# WallDigitalClock.net
KiCad netlist of a schematic drawn in Altium Designer
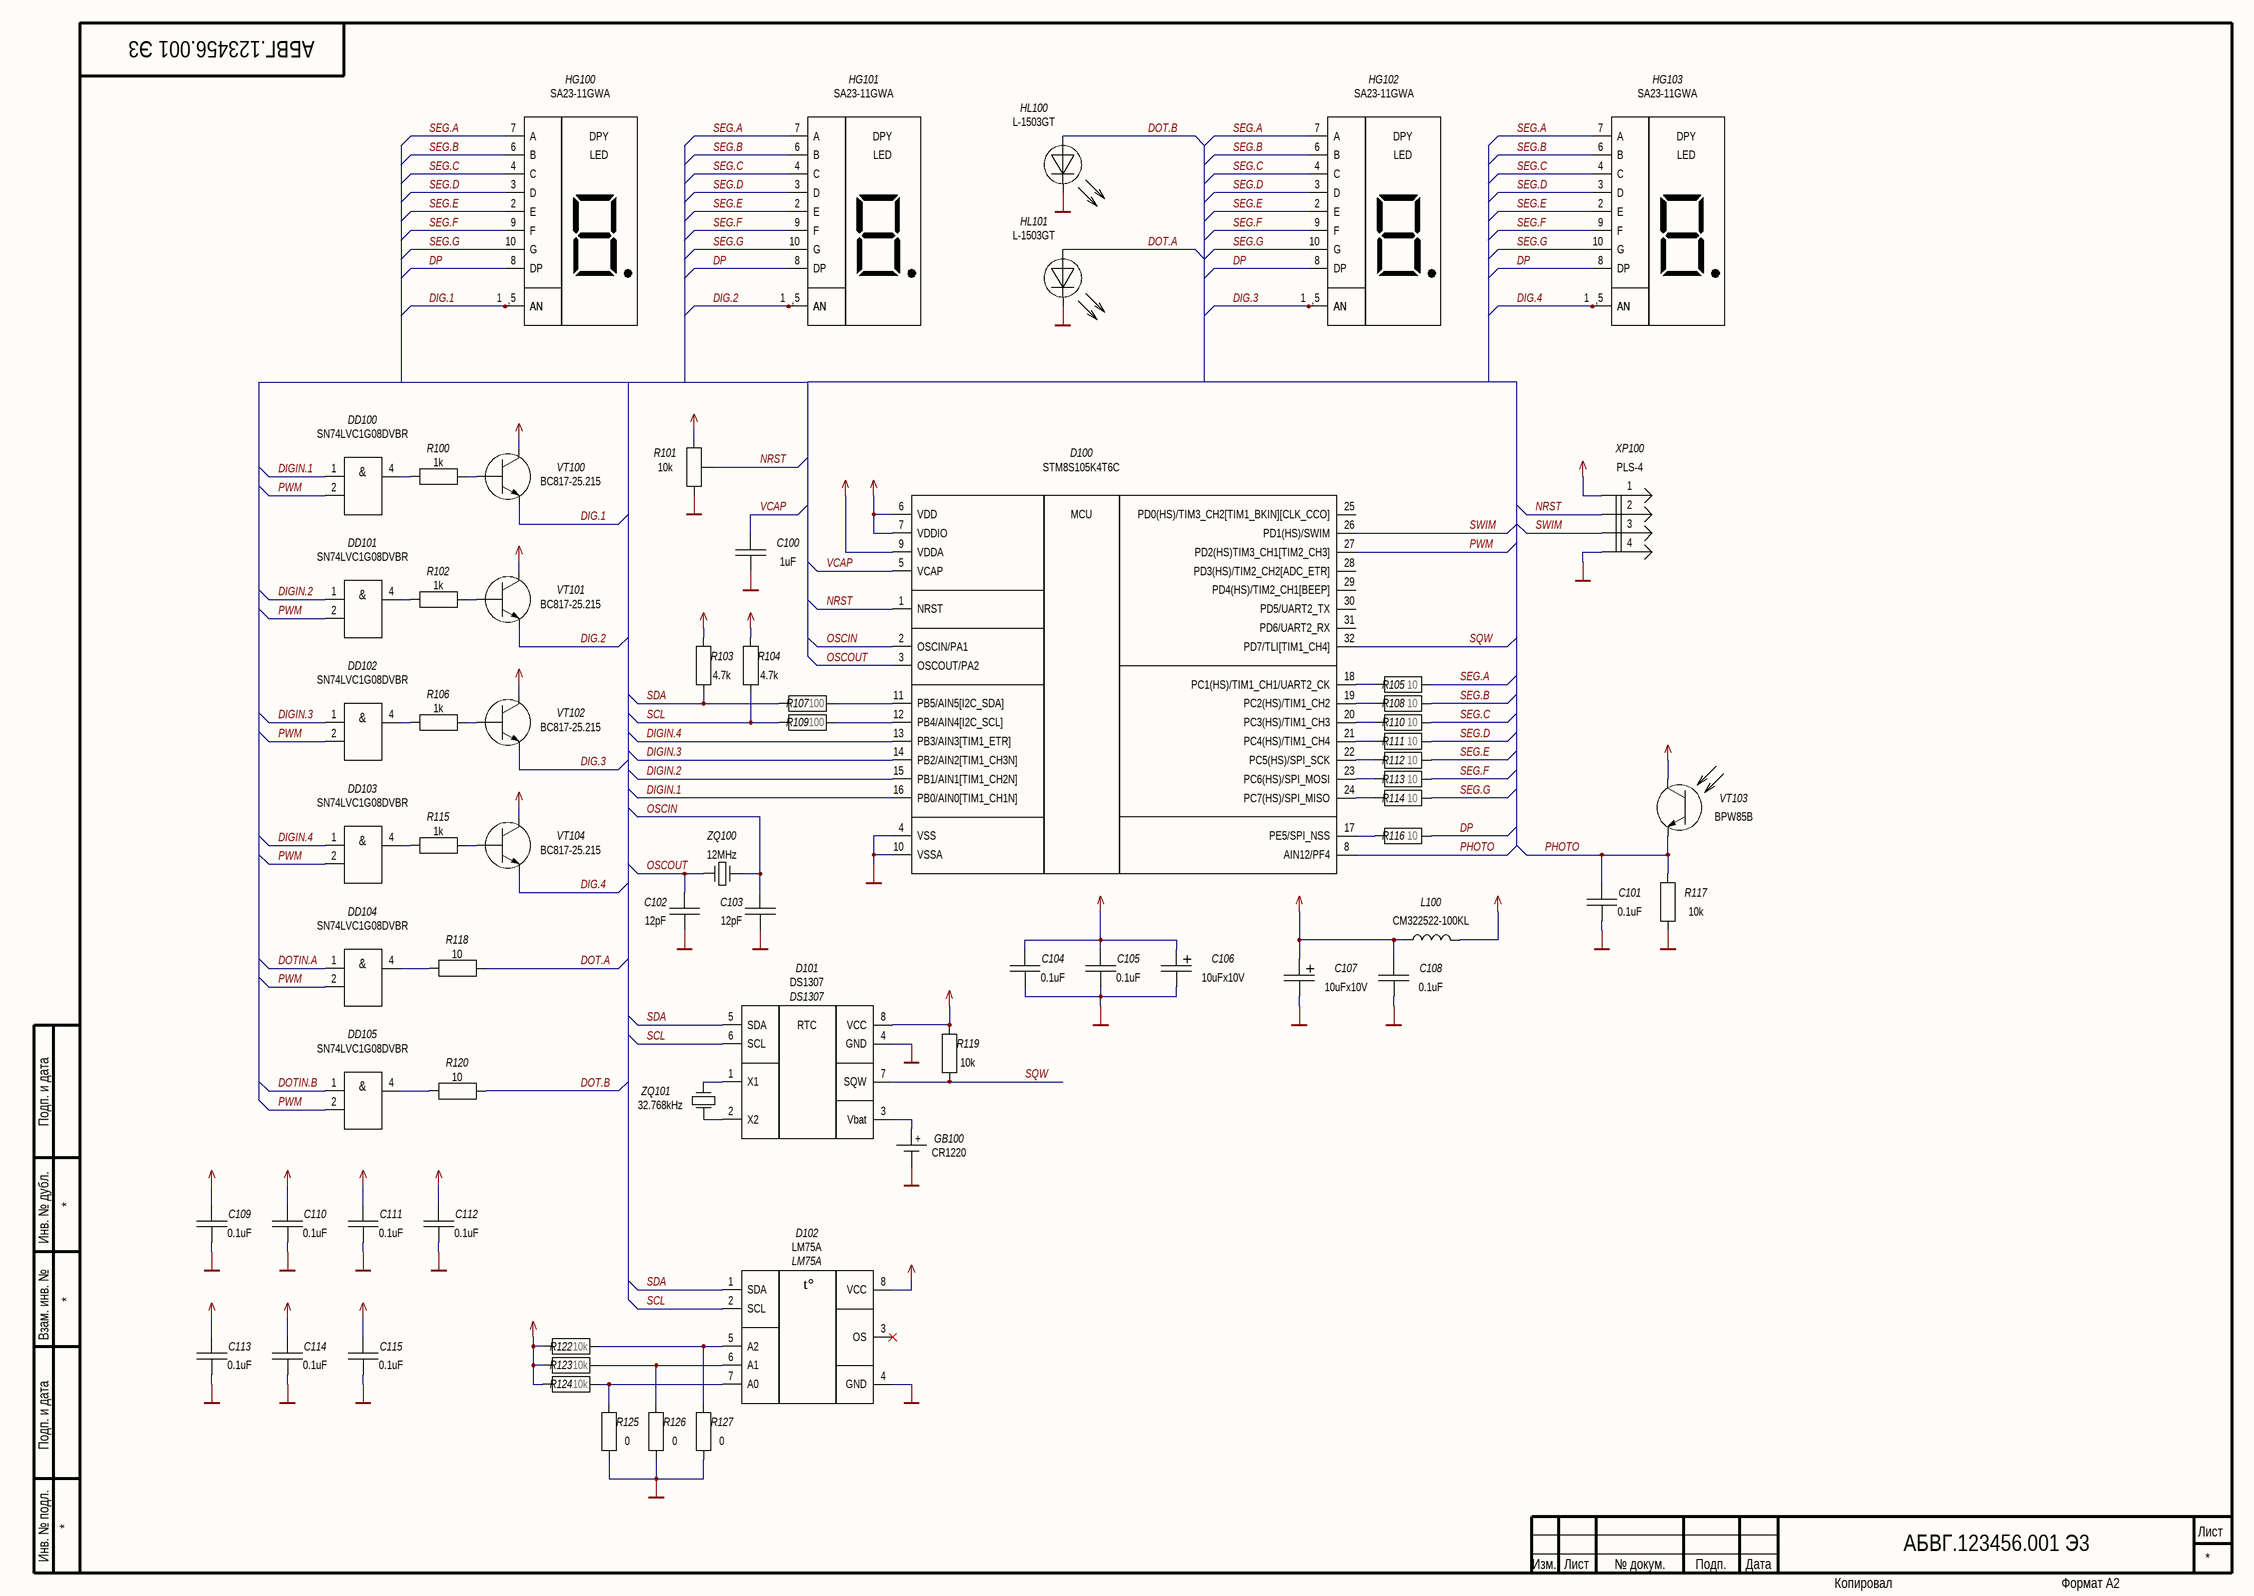
[diagram p0: WallDigitalClock.SchDoc]

(export (version "E")
  (design (tool "Eeschema 10.0.6"))
  (components
    (comp (ref "C100")
      (value "1uF")
      (footprint "CAP0603RS")
      (fields (field (name "Comment") "Capacitor"))
      (libsource (lib "Capacitor") (part "Capacitor"))
    )
    (comp (ref "C101")
      (value "0.1uF")
      (footprint "CAP0603RS")
      (fields (field (name "Comment") "Capacitor"))
      (libsource (lib "Capacitor") (part "Capacitor"))
    )
    (comp (ref "C102")
      (value "12pF")
      (footprint "CAP0603RS")
      (fields (field (name "Comment") "Capacitor"))
      (libsource (lib "Capacitor") (part "Capacitor"))
    )
    (comp (ref "C103")
      (value "12pF")
      (footprint "CAP0603RS")
      (fields (field (name "Comment") "Capacitor"))
      (libsource (lib "Capacitor") (part "Capacitor"))
    )
    (comp (ref "C104")
      (value "0.1uF")
      (footprint "CAP0603RS")
      (fields (field (name "Comment") "Capacitor"))
      (libsource (lib "Capacitor") (part "Capacitor"))
    )
    (comp (ref "C105")
      (value "0.1uF")
      (footprint "CAP0603RS")
      (fields (field (name "Comment") "Capacitor"))
      (libsource (lib "Capacitor") (part "Capacitor"))
    )
    (comp (ref "C106")
      (value "10uFx10V")
      (footprint "Type-C")
      (fields (field (name "MANUFACTURER") "Vishay") (field (name "Comment") "Capacitor_Pol"))
      (libsource (lib "Capacitor") (part "Capacitor_Pol"))
    )
    (comp (ref "C107")
      (value "10uFx10V")
      (footprint "Type-C")
      (fields (field (name "MANUFACTURER") "Vishay") (field (name "Comment") "Capacitor_Pol"))
      (libsource (lib "Capacitor") (part "Capacitor_Pol"))
    )
    (comp (ref "C108")
      (value "0.1uF")
      (footprint "CAP0603RS")
      (fields (field (name "Comment") "Capacitor"))
      (libsource (lib "Capacitor") (part "Capacitor"))
    )
    (comp (ref "C109")
      (value "0.1uF")
      (footprint "CAP0603RS")
      (fields (field (name "Comment") "Capacitor"))
      (libsource (lib "Capacitor") (part "Capacitor"))
    )
    (comp (ref "C110")
      (value "0.1uF")
      (footprint "CAP0603RS")
      (fields (field (name "Comment") "Capacitor"))
      (libsource (lib "Capacitor") (part "Capacitor"))
    )
    (comp (ref "C111")
      (value "0.1uF")
      (footprint "CAP0603RS")
      (fields (field (name "Comment") "Capacitor"))
      (libsource (lib "Capacitor") (part "Capacitor"))
    )
    (comp (ref "C112")
      (value "0.1uF")
      (footprint "CAP0603RS")
      (fields (field (name "Comment") "Capacitor"))
      (libsource (lib "Capacitor") (part "Capacitor"))
    )
    (comp (ref "C113")
      (value "0.1uF")
      (footprint "CAP0603RS")
      (fields (field (name "Comment") "Capacitor"))
      (libsource (lib "Capacitor") (part "Capacitor"))
    )
    (comp (ref "C114")
      (value "0.1uF")
      (footprint "CAP0603RS")
      (fields (field (name "Comment") "Capacitor"))
      (libsource (lib "Capacitor") (part "Capacitor"))
    )
    (comp (ref "C115")
      (value "0.1uF")
      (footprint "CAP0603RS")
      (fields (field (name "Comment") "Capacitor"))
      (libsource (lib "Capacitor") (part "Capacitor"))
    )
    (comp (ref "D100")
      (value "STM8S105K4T6C")
      (footprint "LQFP32")
      (description "MCU 8bit, STM8 CISC, Package LQFP-32")
      (fields (field (name "MANUFACTURER") "ST Microelectronics"))
      (libsource (lib "IC_STM8") (part "STM8S105K4T6C"))
    )
    (comp (ref "D101")
      (value "DS1307")
      (footprint "SO8")
      (description "Real-time clock (RTC)")
      (fields (field (name "ALTIUM_VALUE") "DS1307"))
      (libsource (lib "IC_Sensor") (part "DS1307"))
    )
    (comp (ref "D102")
      (value "LM75A")
      (footprint "SO8")
      (description "Digital temperature sensor and thermal watchdog")
      (fields (field (name "ALTIUM_VALUE") "LM75A"))
      (libsource (lib "IC_Sensor") (part "LM75A"))
    )
    (comp (ref "DD100")
      (value "SN74LVC1G08DVBR")
      (footprint "SOT23-5")
      (description "Single 2-Input Positive-AND Gate")
      (fields (field (name "MANUFACTURER") "Texas Instruments") (field (name "Comment") "SN74LVC1G08"))
      (libsource (lib "IC_Logic") (part "SN74LVC1G08"))
    )
    (comp (ref "DD101")
      (value "SN74LVC1G08DVBR")
      (footprint "SOT23-5")
      (description "Single 2-Input Positive-AND Gate")
      (fields (field (name "MANUFACTURER") "Texas Instruments") (field (name "Comment") "SN74LVC1G08"))
      (libsource (lib "IC_Logic") (part "SN74LVC1G08"))
    )
    (comp (ref "DD102")
      (value "SN74LVC1G08DVBR")
      (footprint "SOT23-5")
      (description "Single 2-Input Positive-AND Gate")
      (fields (field (name "MANUFACTURER") "Texas Instruments") (field (name "Comment") "SN74LVC1G08"))
      (libsource (lib "IC_Logic") (part "SN74LVC1G08"))
    )
    (comp (ref "DD103")
      (value "SN74LVC1G08DVBR")
      (footprint "SOT23-5")
      (description "Single 2-Input Positive-AND Gate")
      (fields (field (name "MANUFACTURER") "Texas Instruments") (field (name "Comment") "SN74LVC1G08"))
      (libsource (lib "IC_Logic") (part "SN74LVC1G08"))
    )
    (comp (ref "DD104")
      (value "SN74LVC1G08DVBR")
      (footprint "SOT23-5")
      (description "Single 2-Input Positive-AND Gate")
      (fields (field (name "MANUFACTURER") "Texas Instruments") (field (name "Comment") "SN74LVC1G08"))
      (libsource (lib "IC_Logic") (part "SN74LVC1G08"))
    )
    (comp (ref "DD105")
      (value "SN74LVC1G08DVBR")
      (footprint "SOT23-5")
      (description "Single 2-Input Positive-AND Gate")
      (fields (field (name "MANUFACTURER") "Texas Instruments") (field (name "Comment") "SN74LVC1G08"))
      (libsource (lib "IC_Logic") (part "SN74LVC1G08"))
    )
    (comp (ref "GB100")
      (value "CR1220")
      (footprint "CR1220_HOLDER")
      (description "Holder for single battery")
      (libsource (lib "Device") (part "Single_Battety"))
    )
    (comp (ref "HG100")
      (value "SA23-11GWA")
      (footprint "SA23-11")
      (description "Single Digit Numeric Display 57mm (2.3INCH), Common Anode")
      (fields (field (name "MANUFACTURER") "Kingbright") (field (name "Comment") "SA23-11"))
      (libsource (lib "Display") (part "SA23-11"))
    )
    (comp (ref "HG101")
      (value "SA23-11GWA")
      (footprint "SA23-11")
      (description "Single Digit Numeric Display 57mm (2.3INCH), Common Anode")
      (fields (field (name "MANUFACTURER") "Kingbright") (field (name "Comment") "SA23-11"))
      (libsource (lib "Display") (part "SA23-11"))
    )
    (comp (ref "HG102")
      (value "SA23-11GWA")
      (footprint "SA23-11")
      (description "Single Digit Numeric Display 57mm (2.3INCH), Common Anode")
      (fields (field (name "MANUFACTURER") "Kingbright") (field (name "Comment") "SA23-11"))
      (libsource (lib "Display") (part "SA23-11"))
    )
    (comp (ref "HG103")
      (value "SA23-11GWA")
      (footprint "SA23-11")
      (description "Single Digit Numeric Display 57mm (2.3INCH), Common Anode")
      (fields (field (name "MANUFACTURER") "Kingbright") (field (name "Comment") "SA23-11"))
      (libsource (lib "Display") (part "SA23-11"))
    )
    (comp (ref "HL100")
      (value "L-1503GT")
      (footprint "LED_5mm_Green")
      (fields (field (name "Comment") "Green"))
      (libsource (lib "Opto") (part "LED"))
    )
    (comp (ref "HL101")
      (value "L-1503GT")
      (footprint "LED_5mm_Green")
      (fields (field (name "Comment") "Green"))
      (libsource (lib "Opto") (part "LED"))
    )
    (comp (ref "L100")
      (value "CM322522-100KL")
      (footprint "IND1210")
      (fields (field (name "MANUFACTURER") "Bourns") (field (name "Comment") "Inductor"))
      (libsource (lib "Inductors") (part "Inductor"))
    )
    (comp (ref "R100")
      (value "1k")
      (footprint "RES0603WS")
      (fields (field (name "Comment") "Resistor"))
      (libsource (lib "") (part "Resistor_1"))
    )
    (comp (ref "R101")
      (value "10k")
      (footprint "RES0603JMP-RS")
      (description "Jumper two way on resistor")
      (fields (field (name "Comment") "Res_JMP"))
      (libsource (lib "Resistor") (part "Res_JMP"))
    )
    (comp (ref "R102")
      (value "1k")
      (footprint "RES0603WS")
      (fields (field (name "Comment") "Resistor"))
      (libsource (lib "") (part "Resistor_1"))
    )
    (comp (ref "R103")
      (value "4.7k")
      (footprint "RES0805WS")
      (fields (field (name "Comment") "Resistor"))
      (libsource (lib "Resistor") (part "Resistor"))
    )
    (comp (ref "R104")
      (value "4.7k")
      (footprint "RES0805WS")
      (fields (field (name "Comment") "Resistor"))
      (libsource (lib "Resistor") (part "Resistor"))
    )
    (comp (ref "R105")
      (value "10")
      (footprint "RES0805RS")
      (fields (field (name "Comment") "Resistor"))
      (libsource (lib "") (part "Resistor_1"))
    )
    (comp (ref "R106")
      (value "1k")
      (footprint "RES0603WS")
      (fields (field (name "Comment") "Resistor"))
      (libsource (lib "") (part "Resistor_1"))
    )
    (comp (ref "R107")
      (value "100")
      (footprint "RES0603WS")
      (fields (field (name "Comment") "Resistor"))
      (libsource (lib "") (part "Resistor_1"))
    )
    (comp (ref "R108")
      (value "10")
      (footprint "RES0805RS")
      (fields (field (name "Comment") "Resistor"))
      (libsource (lib "") (part "Resistor_1"))
    )
    (comp (ref "R109")
      (value "100")
      (footprint "RES0603WS")
      (fields (field (name "Comment") "Resistor"))
      (libsource (lib "") (part "Resistor_1"))
    )
    (comp (ref "R110")
      (value "10")
      (footprint "RES0805RS")
      (fields (field (name "Comment") "Resistor"))
      (libsource (lib "") (part "Resistor_1"))
    )
    (comp (ref "R111")
      (value "10")
      (footprint "RES0805RS")
      (fields (field (name "Comment") "Resistor"))
      (libsource (lib "") (part "Resistor_1"))
    )
    (comp (ref "R112")
      (value "10")
      (footprint "RES0805RS")
      (fields (field (name "Comment") "Resistor"))
      (libsource (lib "") (part "Resistor_1"))
    )
    (comp (ref "R113")
      (value "10")
      (footprint "RES0805RS")
      (fields (field (name "Comment") "Resistor"))
      (libsource (lib "") (part "Resistor_1"))
    )
    (comp (ref "R114")
      (value "10")
      (footprint "RES0805RS")
      (fields (field (name "Comment") "Resistor"))
      (libsource (lib "") (part "Resistor_1"))
    )
    (comp (ref "R115")
      (value "1k")
      (footprint "RES0603WS")
      (fields (field (name "Comment") "Resistor"))
      (libsource (lib "") (part "Resistor_1"))
    )
    (comp (ref "R116")
      (value "10")
      (footprint "RES0805RS")
      (fields (field (name "Comment") "Resistor"))
      (libsource (lib "") (part "Resistor_1"))
    )
    (comp (ref "R117")
      (value "10k")
      (footprint "RES0603WS")
      (fields (field (name "Comment") "Resistor"))
      (libsource (lib "Resistor") (part "Resistor"))
    )
    (comp (ref "R118")
      (value "10")
      (footprint "RES0603WS")
      (fields (field (name "Comment") "Resistor"))
      (libsource (lib "") (part "Resistor_1"))
    )
    (comp (ref "R119")
      (value "10k")
      (footprint "RES0805WS")
      (fields (field (name "Comment") "Resistor"))
      (libsource (lib "Resistor") (part "Resistor"))
    )
    (comp (ref "R120")
      (value "10")
      (footprint "RES0603WS")
      (fields (field (name "Comment") "Resistor"))
      (libsource (lib "") (part "Resistor_1"))
    )
    (comp (ref "R122")
      (value "10k")
      (footprint "RES0603WS")
      (fields (field (name "Comment") "Resistor"))
      (libsource (lib "") (part "Resistor_1"))
    )
    (comp (ref "R123")
      (value "10k")
      (footprint "RES0603WS")
      (fields (field (name "Comment") "Resistor"))
      (libsource (lib "") (part "Resistor_1"))
    )
    (comp (ref "R124")
      (value "10k")
      (footprint "RES0603WS")
      (fields (field (name "Comment") "Resistor"))
      (libsource (lib "") (part "Resistor_1"))
    )
    (comp (ref "R125")
      (value "0")
      (footprint "RES0603WS")
      (fields (field (name "Comment") "Resistor"))
      (libsource (lib "Resistor") (part "Resistor"))
    )
    (comp (ref "R126")
      (value "0")
      (footprint "RES0603WS")
      (fields (field (name "Comment") "Resistor"))
      (libsource (lib "Resistor") (part "Resistor"))
    )
    (comp (ref "R127")
      (value "0")
      (footprint "RES0603WS")
      (fields (field (name "Comment") "Resistor"))
      (libsource (lib "Resistor") (part "Resistor"))
    )
    (comp (ref "VT100")
      (value "BC817-25.215")
      (footprint "SOT-23")
      (fields (field (name "Comment") "NPN"))
      (libsource (lib "Semiconductor") (part "NPN"))
    )
    (comp (ref "VT101")
      (value "BC817-25.215")
      (footprint "SOT-23")
      (fields (field (name "Comment") "NPN"))
      (libsource (lib "Semiconductor") (part "NPN"))
    )
    (comp (ref "VT102")
      (value "BC817-25.215")
      (footprint "SOT-23")
      (fields (field (name "Comment") "NPN"))
      (libsource (lib "Semiconductor") (part "NPN"))
    )
    (comp (ref "VT103")
      (value "BPW85B")
      (footprint "LED_5mm_Clear")
      (fields (field (name "MANUFACTURER") "Vishay") (field (name "Comment") "Photo_Transistor"))
      (libsource (lib "Opto") (part "Photo_Transistor"))
    )
    (comp (ref "VT104")
      (value "BC817-25.215")
      (footprint "SOT-23")
      (fields (field (name "Comment") "NPN"))
      (libsource (lib "Semiconductor") (part "NPN"))
    )
    (comp (ref "XP100")
      (value "PLS-4")
      (footprint "PLS-4-2.54")
      (fields (field (name "Comment") "MaleConn_4_pin"))
      (libsource (lib "Connectors") (part "MaleConn_4_pin"))
    )
    (comp (ref "ZQ100")
      (value "12MHz")
      (footprint "HC-49SM")
      (libsource (lib "Generators") (part "Crystal_Oscillator"))
    )
    (comp (ref "ZQ101")
      (value "32.768kHz")
      (footprint "KX-327S")
      (libsource (lib "") (part "Crystal_Oscillator_1"))
    )
  )
  (nets
    (net (code "1") (name "/DIG.1") (class "Default")
      (node (ref "HG100") (pin "1") (pinfunction "AN_1") (pintype "passive"))
      (node (ref "HG100") (pin "5") (pinfunction "AN_5") (pintype "passive"))
      (node (ref "VT100") (pin "E") (pinfunction "E_E") (pintype "passive"))
    )
    (net (code "2") (name "/DIG.2") (class "Default")
      (node (ref "HG101") (pin "1") (pinfunction "AN_1") (pintype "passive"))
      (node (ref "HG101") (pin "5") (pinfunction "AN_5") (pintype "passive"))
      (node (ref "VT101") (pin "E") (pinfunction "E_E") (pintype "passive"))
    )
    (net (code "3") (name "/DIG.3") (class "Default")
      (node (ref "HG102") (pin "1") (pinfunction "AN_1") (pintype "passive"))
      (node (ref "HG102") (pin "5") (pinfunction "AN_5") (pintype "passive"))
      (node (ref "VT102") (pin "E") (pinfunction "E_E") (pintype "passive"))
    )
    (net (code "4") (name "/DIG.4") (class "Default")
      (node (ref "HG103") (pin "1") (pinfunction "AN_1") (pintype "passive"))
      (node (ref "HG103") (pin "5") (pinfunction "AN_5") (pintype "passive"))
      (node (ref "VT104") (pin "E") (pinfunction "E_E") (pintype "passive"))
    )
    (net (code "5") (name "/DIGIN.1") (class "Default")
      (node (ref "D100") (pin "16") (pinfunction "PB0/AIN0[TIM1_CH1N]_16") (pintype "passive"))
      (node (ref "DD100") (pin "1") (pinfunction "A_1") (pintype "passive"))
    )
    (net (code "6") (name "/DIGIN.2") (class "Default")
      (node (ref "D100") (pin "15") (pinfunction "PB1/AIN1[TIM1_CH2N]_15") (pintype "passive"))
      (node (ref "DD101") (pin "1") (pinfunction "A_1") (pintype "passive"))
    )
    (net (code "7") (name "/DIGIN.3") (class "Default")
      (node (ref "D100") (pin "14") (pinfunction "PB2/AIN2[TIM1_CH3N]_14") (pintype "passive"))
      (node (ref "DD102") (pin "1") (pinfunction "A_1") (pintype "passive"))
    )
    (net (code "8") (name "/DIGIN.4") (class "Default")
      (node (ref "D100") (pin "13") (pinfunction "PB3/AIN3[TIM1_ETR]_13") (pintype "passive"))
      (node (ref "DD103") (pin "1") (pinfunction "A_1") (pintype "passive"))
    )
    (net (code "9") (name "/DOT.A") (class "Default")
      (node (ref "HL101") (pin "2") (pinfunction "2_2") (pintype "passive"))
      (node (ref "R118") (pin "2") (pinfunction "2_2") (pintype "passive"))
    )
    (net (code "10") (name "/DOT.B") (class "Default")
      (node (ref "HL100") (pin "2") (pinfunction "2_2") (pintype "passive"))
      (node (ref "R120") (pin "2") (pinfunction "2_2") (pintype "passive"))
    )
    (net (code "11") (name "/DOTIN.A") (class "Default")
      (node (ref "DD104") (pin "1") (pinfunction "A_1") (pintype "passive"))
    )
    (net (code "12") (name "/DOTIN.B") (class "Default")
      (node (ref "DD105") (pin "1") (pinfunction "A_1") (pintype "passive"))
    )
    (net (code "13") (name "/DP") (class "Default")
      (node (ref "HG100") (pin "8") (pinfunction "DP_8") (pintype "passive"))
      (node (ref "HG101") (pin "8") (pinfunction "DP_8") (pintype "passive"))
      (node (ref "HG102") (pin "8") (pinfunction "DP_8") (pintype "passive"))
      (node (ref "HG103") (pin "8") (pinfunction "DP_8") (pintype "passive"))
      (node (ref "R116") (pin "2") (pinfunction "2_2") (pintype "passive"))
    )
    (net (code "14") (name "/NRST") (class "Default")
      (node (ref "D100") (pin "1") (pinfunction "NRST_1") (pintype "passive"))
      (node (ref "R101") (pin "2") (pinfunction "2_2") (pintype "passive"))
      (node (ref "XP100") (pin "2") (pinfunction "2_2") (pintype "passive"))
    )
    (net (code "15") (name "/OSCIN") (class "Default")
      (node (ref "C103") (pin "1") (pinfunction "1_1") (pintype "passive"))
      (node (ref "D100") (pin "2") (pinfunction "OSCIN/PA1_2") (pintype "passive"))
      (node (ref "ZQ100") (pin "2") (pinfunction "2_2") (pintype "passive"))
    )
    (net (code "16") (name "/OSCOUT") (class "Default")
      (node (ref "C102") (pin "1") (pinfunction "1_1") (pintype "passive"))
      (node (ref "D100") (pin "3") (pinfunction "OSCOUT/PA2_3") (pintype "passive"))
      (node (ref "ZQ100") (pin "1") (pinfunction "1_1") (pintype "passive"))
    )
    (net (code "17") (name "/PHOTO") (class "Default")
      (node (ref "C101") (pin "1") (pinfunction "1_1") (pintype "passive"))
      (node (ref "D100") (pin "8") (pinfunction "AIN12/PF4_8") (pintype "passive"))
      (node (ref "R117") (pin "1") (pinfunction "1_1") (pintype "passive"))
      (node (ref "VT103") (pin "E") (pinfunction "E_E") (pintype "passive"))
    )
    (net (code "18") (name "/PWM") (class "Default")
      (node (ref "D100") (pin "27") (pinfunction "PD2(HS)TIM3_CH1[TIM2_CH3]_27") (pintype "passive"))
      (node (ref "DD100") (pin "2") (pinfunction "B_2") (pintype "passive"))
      (node (ref "DD101") (pin "2") (pinfunction "B_2") (pintype "passive"))
      (node (ref "DD102") (pin "2") (pinfunction "B_2") (pintype "passive"))
      (node (ref "DD103") (pin "2") (pinfunction "B_2") (pintype "passive"))
      (node (ref "DD104") (pin "2") (pinfunction "B_2") (pintype "passive"))
      (node (ref "DD105") (pin "2") (pinfunction "B_2") (pintype "passive"))
    )
    (net (code "19") (name "/SCL") (class "Default")
      (node (ref "D101") (pin "6") (pinfunction "SCL_6") (pintype "passive"))
      (node (ref "D102") (pin "2") (pinfunction "SCL_2") (pintype "passive"))
      (node (ref "R104") (pin "2") (pinfunction "2_2") (pintype "passive"))
      (node (ref "R109") (pin "1") (pinfunction "1_1") (pintype "passive"))
    )
    (net (code "20") (name "/SDA") (class "Default")
      (node (ref "D101") (pin "5") (pinfunction "SDA_5") (pintype "passive"))
      (node (ref "D102") (pin "1") (pinfunction "SDA_1") (pintype "passive"))
      (node (ref "R103") (pin "2") (pinfunction "2_2") (pintype "passive"))
      (node (ref "R107") (pin "1") (pinfunction "1_1") (pintype "passive"))
    )
    (net (code "21") (name "/SEG.A") (class "Default")
      (node (ref "HG100") (pin "7") (pinfunction "A_7") (pintype "passive"))
      (node (ref "HG101") (pin "7") (pinfunction "A_7") (pintype "passive"))
      (node (ref "HG102") (pin "7") (pinfunction "A_7") (pintype "passive"))
      (node (ref "HG103") (pin "7") (pinfunction "A_7") (pintype "passive"))
      (node (ref "R105") (pin "2") (pinfunction "2_2") (pintype "passive"))
    )
    (net (code "22") (name "/SEG.B") (class "Default")
      (node (ref "HG100") (pin "6") (pinfunction "B_6") (pintype "passive"))
      (node (ref "HG101") (pin "6") (pinfunction "B_6") (pintype "passive"))
      (node (ref "HG102") (pin "6") (pinfunction "B_6") (pintype "passive"))
      (node (ref "HG103") (pin "6") (pinfunction "B_6") (pintype "passive"))
      (node (ref "R108") (pin "2") (pinfunction "2_2") (pintype "passive"))
    )
    (net (code "23") (name "/SEG.C") (class "Default")
      (node (ref "HG100") (pin "4") (pinfunction "C_4") (pintype "passive"))
      (node (ref "HG101") (pin "4") (pinfunction "C_4") (pintype "passive"))
      (node (ref "HG102") (pin "4") (pinfunction "C_4") (pintype "passive"))
      (node (ref "HG103") (pin "4") (pinfunction "C_4") (pintype "passive"))
      (node (ref "R110") (pin "2") (pinfunction "2_2") (pintype "passive"))
    )
    (net (code "24") (name "/SEG.D") (class "Default")
      (node (ref "HG100") (pin "3") (pinfunction "D_3") (pintype "passive"))
      (node (ref "HG101") (pin "3") (pinfunction "D_3") (pintype "passive"))
      (node (ref "HG102") (pin "3") (pinfunction "D_3") (pintype "passive"))
      (node (ref "HG103") (pin "3") (pinfunction "D_3") (pintype "passive"))
      (node (ref "R111") (pin "2") (pinfunction "2_2") (pintype "passive"))
    )
    (net (code "25") (name "/SEG.E") (class "Default")
      (node (ref "HG100") (pin "2") (pinfunction "E_2") (pintype "passive"))
      (node (ref "HG101") (pin "2") (pinfunction "E_2") (pintype "passive"))
      (node (ref "HG102") (pin "2") (pinfunction "E_2") (pintype "passive"))
      (node (ref "HG103") (pin "2") (pinfunction "E_2") (pintype "passive"))
      (node (ref "R112") (pin "2") (pinfunction "2_2") (pintype "passive"))
    )
    (net (code "26") (name "/SEG.F") (class "Default")
      (node (ref "HG100") (pin "9") (pinfunction "F_9") (pintype "passive"))
      (node (ref "HG101") (pin "9") (pinfunction "F_9") (pintype "passive"))
      (node (ref "HG102") (pin "9") (pinfunction "F_9") (pintype "passive"))
      (node (ref "HG103") (pin "9") (pinfunction "F_9") (pintype "passive"))
      (node (ref "R113") (pin "2") (pinfunction "2_2") (pintype "passive"))
    )
    (net (code "27") (name "/SEG.G") (class "Default")
      (node (ref "HG100") (pin "10") (pinfunction "G_10") (pintype "passive"))
      (node (ref "HG101") (pin "10") (pinfunction "G_10") (pintype "passive"))
      (node (ref "HG102") (pin "10") (pinfunction "G_10") (pintype "passive"))
      (node (ref "HG103") (pin "10") (pinfunction "G_10") (pintype "passive"))
      (node (ref "R114") (pin "2") (pinfunction "2_2") (pintype "passive"))
    )
    (net (code "28") (name "/SQW") (class "Default")
      (node (ref "D100") (pin "32") (pinfunction "PD7/TLI[TIM1_CH4]_32") (pintype "passive"))
      (node (ref "D101") (pin "7") (pinfunction "SQW_7") (pintype "passive"))
      (node (ref "R119") (pin "2") (pinfunction "2_2") (pintype "passive"))
    )
    (net (code "29") (name "/SWIM") (class "Default")
      (node (ref "D100") (pin "26") (pinfunction "PD1(HS)/SWIM_26") (pintype "passive"))
      (node (ref "XP100") (pin "3") (pinfunction "3_3") (pintype "passive"))
    )
    (net (code "30") (name "/VCAP") (class "Default")
      (node (ref "C100") (pin "1") (pinfunction "1_1") (pintype "passive"))
      (node (ref "D100") (pin "5") (pinfunction "VCAP_5") (pintype "passive"))
    )
    (net (code "31") (name "GND") (class "Default")
      (node (ref "C100") (pin "2") (pinfunction "2_2") (pintype "passive"))
      (node (ref "C101") (pin "2") (pinfunction "2_2") (pintype "passive"))
      (node (ref "C102") (pin "2") (pinfunction "2_2") (pintype "passive"))
      (node (ref "C103") (pin "2") (pinfunction "2_2") (pintype "passive"))
      (node (ref "C104") (pin "2") (pinfunction "2_2") (pintype "passive"))
      (node (ref "C105") (pin "2") (pinfunction "2_2") (pintype "passive"))
      (node (ref "C106") (pin "2") (pinfunction "2_2") (pintype "passive"))
      (node (ref "C107") (pin "2") (pinfunction "2_2") (pintype "passive"))
      (node (ref "C108") (pin "2") (pinfunction "2_2") (pintype "passive"))
      (node (ref "C109") (pin "2") (pinfunction "2_2") (pintype "passive"))
      (node (ref "C110") (pin "2") (pinfunction "2_2") (pintype "passive"))
      (node (ref "C111") (pin "2") (pinfunction "2_2") (pintype "passive"))
      (node (ref "C112") (pin "2") (pinfunction "2_2") (pintype "passive"))
      (node (ref "C113") (pin "2") (pinfunction "2_2") (pintype "passive"))
      (node (ref "C114") (pin "2") (pinfunction "2_2") (pintype "passive"))
      (node (ref "C115") (pin "2") (pinfunction "2_2") (pintype "passive"))
      (node (ref "D100") (pin "10") (pinfunction "VSSA_10") (pintype "passive"))
      (node (ref "D100") (pin "4") (pinfunction "VSS_4") (pintype "passive"))
      (node (ref "D101") (pin "4") (pinfunction "GND_4") (pintype "passive"))
      (node (ref "D102") (pin "4") (pinfunction "GND_4") (pintype "passive"))
      (node (ref "DD100") (pin "3") (pinfunction "GND_3") (pintype "power_in"))
      (node (ref "DD101") (pin "3") (pinfunction "GND_3") (pintype "power_in"))
      (node (ref "DD102") (pin "3") (pinfunction "GND_3") (pintype "power_in"))
      (node (ref "DD103") (pin "3") (pinfunction "GND_3") (pintype "power_in"))
      (node (ref "DD104") (pin "3") (pinfunction "GND_3") (pintype "power_in"))
      (node (ref "DD105") (pin "3") (pinfunction "GND_3") (pintype "power_in"))
      (node (ref "GB100") (pin "2") (pinfunction "2_2") (pintype "passive"))
      (node (ref "HL100") (pin "1") (pinfunction "1_1") (pintype "passive"))
      (node (ref "HL101") (pin "1") (pinfunction "1_1") (pintype "passive"))
      (node (ref "R101") (pin "3") (pinfunction "3_3") (pintype "passive"))
      (node (ref "R117") (pin "2") (pinfunction "2_2") (pintype "passive"))
      (node (ref "R125") (pin "2") (pinfunction "2_2") (pintype "passive"))
      (node (ref "R126") (pin "2") (pinfunction "2_2") (pintype "passive"))
      (node (ref "R127") (pin "2") (pinfunction "2_2") (pintype "passive"))
      (node (ref "XP100") (pin "4") (pinfunction "4_4") (pintype "passive"))
    )
    (net (code "32") (name "Net-(D100-PB4{slash}AIN4[I2C_SCL])") (class "Default")
      (node (ref "D100") (pin "12") (pinfunction "PB4/AIN4[I2C_SCL]_12") (pintype "passive"))
      (node (ref "R109") (pin "2") (pinfunction "2_2") (pintype "passive"))
    )
    (net (code "33") (name "Net-(D100-PB5{slash}AIN5[I2C_SDA])") (class "Default")
      (node (ref "D100") (pin "11") (pinfunction "PB5/AIN5[I2C_SDA]_11") (pintype "passive"))
      (node (ref "R107") (pin "2") (pinfunction "2_2") (pintype "passive"))
    )
    (net (code "34") (name "Net-(D100-PC1(HS){slash}TIM1_CH1{slash}UART2_CK)") (class "Default")
      (node (ref "D100") (pin "18") (pinfunction "PC1(HS)/TIM1_CH1/UART2_CK_18") (pintype "passive"))
      (node (ref "R105") (pin "1") (pinfunction "1_1") (pintype "passive"))
    )
    (net (code "35") (name "Net-(D100-PC2(HS){slash}TIM1_CH2)") (class "Default")
      (node (ref "D100") (pin "19") (pinfunction "PC2(HS)/TIM1_CH2_19") (pintype "passive"))
      (node (ref "R108") (pin "1") (pinfunction "1_1") (pintype "passive"))
    )
    (net (code "36") (name "Net-(D100-PC3(HS){slash}TIM1_CH3)") (class "Default")
      (node (ref "D100") (pin "20") (pinfunction "PC3(HS)/TIM1_CH3_20") (pintype "passive"))
      (node (ref "R110") (pin "1") (pinfunction "1_1") (pintype "passive"))
    )
    (net (code "37") (name "Net-(D100-PC4(HS){slash}TIM1_CH4)") (class "Default")
      (node (ref "D100") (pin "21") (pinfunction "PC4(HS)/TIM1_CH4_21") (pintype "passive"))
      (node (ref "R111") (pin "1") (pinfunction "1_1") (pintype "passive"))
    )
    (net (code "38") (name "Net-(D100-PC5(HS){slash}SPI_SCK)") (class "Default")
      (node (ref "D100") (pin "22") (pinfunction "PC5(HS)/SPI_SCK_22") (pintype "passive"))
      (node (ref "R112") (pin "1") (pinfunction "1_1") (pintype "passive"))
    )
    (net (code "39") (name "Net-(D100-PC6(HS){slash}SPI_MOSI)") (class "Default")
      (node (ref "D100") (pin "23") (pinfunction "PC6(HS)/SPI_MOSI_23") (pintype "passive"))
      (node (ref "R113") (pin "1") (pinfunction "1_1") (pintype "passive"))
    )
    (net (code "40") (name "Net-(D100-PC7(HS){slash}SPI_MISO)") (class "Default")
      (node (ref "D100") (pin "24") (pinfunction "PC7(HS)/SPI_MISO_24") (pintype "passive"))
      (node (ref "R114") (pin "1") (pinfunction "1_1") (pintype "passive"))
    )
    (net (code "41") (name "Net-(D100-PE5{slash}SPI_NSS)") (class "Default")
      (node (ref "D100") (pin "17") (pinfunction "PE5/SPI_NSS_17") (pintype "passive"))
      (node (ref "R116") (pin "1") (pinfunction "1_1") (pintype "passive"))
    )
    (net (code "42") (name "Net-(D101-Vbat)") (class "Default")
      (node (ref "D101") (pin "3") (pinfunction "Vbat_3") (pintype "passive"))
      (node (ref "GB100") (pin "1") (pinfunction "1_1") (pintype "passive"))
    )
    (net (code "43") (name "Net-(D101-X1)") (class "Default")
      (node (ref "D101") (pin "1") (pinfunction "X1_1") (pintype "passive"))
      (node (ref "ZQ101") (pin "1") (pinfunction "1_1") (pintype "passive"))
    )
    (net (code "44") (name "Net-(D101-X2)") (class "Default")
      (node (ref "D101") (pin "2") (pinfunction "X2_2") (pintype "passive"))
      (node (ref "ZQ101") (pin "2") (pinfunction "2_2") (pintype "passive"))
    )
    (net (code "45") (name "Net-(D102-A0)") (class "Default")
      (node (ref "D102") (pin "7") (pinfunction "A0_7") (pintype "passive"))
      (node (ref "R124") (pin "2") (pinfunction "2_2") (pintype "passive"))
      (node (ref "R125") (pin "1") (pinfunction "1_1") (pintype "passive"))
    )
    (net (code "46") (name "Net-(D102-A1)") (class "Default")
      (node (ref "D102") (pin "6") (pinfunction "A1_6") (pintype "passive"))
      (node (ref "R123") (pin "2") (pinfunction "2_2") (pintype "passive"))
      (node (ref "R126") (pin "1") (pinfunction "1_1") (pintype "passive"))
    )
    (net (code "47") (name "Net-(D102-A2)") (class "Default")
      (node (ref "D102") (pin "5") (pinfunction "A2_5") (pintype "passive"))
      (node (ref "R122") (pin "2") (pinfunction "2_2") (pintype "passive"))
      (node (ref "R127") (pin "1") (pinfunction "1_1") (pintype "passive"))
    )
    (net (code "48") (name "Net-(DD100-Y)") (class "Default")
      (node (ref "DD100") (pin "4") (pinfunction "Y_4") (pintype "passive"))
      (node (ref "R100") (pin "1") (pinfunction "1_1") (pintype "passive"))
    )
    (net (code "49") (name "Net-(DD101-Y)") (class "Default")
      (node (ref "DD101") (pin "4") (pinfunction "Y_4") (pintype "passive"))
      (node (ref "R102") (pin "1") (pinfunction "1_1") (pintype "passive"))
    )
    (net (code "50") (name "Net-(DD102-Y)") (class "Default")
      (node (ref "DD102") (pin "4") (pinfunction "Y_4") (pintype "passive"))
      (node (ref "R106") (pin "1") (pinfunction "1_1") (pintype "passive"))
    )
    (net (code "51") (name "Net-(DD103-Y)") (class "Default")
      (node (ref "DD103") (pin "4") (pinfunction "Y_4") (pintype "passive"))
      (node (ref "R115") (pin "1") (pinfunction "1_1") (pintype "passive"))
    )
    (net (code "52") (name "Net-(DD104-Y)") (class "Default")
      (node (ref "DD104") (pin "4") (pinfunction "Y_4") (pintype "passive"))
      (node (ref "R118") (pin "1") (pinfunction "1_1") (pintype "passive"))
    )
    (net (code "53") (name "Net-(DD105-Y)") (class "Default")
      (node (ref "DD105") (pin "4") (pinfunction "Y_4") (pintype "passive"))
      (node (ref "R120") (pin "1") (pinfunction "1_1") (pintype "passive"))
    )
    (net (code "54") (name "Net-(R100-Pad2)") (class "Default")
      (node (ref "R100") (pin "2") (pinfunction "2_2") (pintype "passive"))
      (node (ref "VT100") (pin "B") (pinfunction "B_B") (pintype "passive"))
    )
    (net (code "55") (name "Net-(R102-Pad2)") (class "Default")
      (node (ref "R102") (pin "2") (pinfunction "2_2") (pintype "passive"))
      (node (ref "VT101") (pin "B") (pinfunction "B_B") (pintype "passive"))
    )
    (net (code "56") (name "Net-(R106-Pad2)") (class "Default")
      (node (ref "R106") (pin "2") (pinfunction "2_2") (pintype "passive"))
      (node (ref "VT102") (pin "B") (pinfunction "B_B") (pintype "passive"))
    )
    (net (code "57") (name "Net-(R115-Pad2)") (class "Default")
      (node (ref "R115") (pin "2") (pinfunction "2_2") (pintype "passive"))
      (node (ref "VT104") (pin "B") (pinfunction "B_B") (pintype "passive"))
    )
    (net (code "58") (name "VCC") (class "Default")
      (node (ref "C104") (pin "1") (pinfunction "1_1") (pintype "passive"))
      (node (ref "C105") (pin "1") (pinfunction "1_1") (pintype "passive"))
      (node (ref "C106") (pin "1") (pinfunction "1_1") (pintype "passive"))
      (node (ref "C109") (pin "1") (pinfunction "1_1") (pintype "passive"))
      (node (ref "C110") (pin "1") (pinfunction "1_1") (pintype "passive"))
      (node (ref "C111") (pin "1") (pinfunction "1_1") (pintype "passive"))
      (node (ref "C112") (pin "1") (pinfunction "1_1") (pintype "passive"))
      (node (ref "C113") (pin "1") (pinfunction "1_1") (pintype "passive"))
      (node (ref "C114") (pin "1") (pinfunction "1_1") (pintype "passive"))
      (node (ref "C115") (pin "1") (pinfunction "1_1") (pintype "passive"))
      (node (ref "D100") (pin "6") (pinfunction "VDD_6") (pintype "passive"))
      (node (ref "D100") (pin "7") (pinfunction "VDDIO_7") (pintype "passive"))
      (node (ref "D101") (pin "8") (pinfunction "VCC_8") (pintype "passive"))
      (node (ref "D102") (pin "8") (pinfunction "VCC_8") (pintype "passive"))
      (node (ref "DD100") (pin "5") (pinfunction "VCC_5") (pintype "power_in"))
      (node (ref "DD101") (pin "5") (pinfunction "VCC_5") (pintype "power_in"))
      (node (ref "DD102") (pin "5") (pinfunction "VCC_5") (pintype "power_in"))
      (node (ref "DD103") (pin "5") (pinfunction "VCC_5") (pintype "power_in"))
      (node (ref "DD104") (pin "5") (pinfunction "VCC_5") (pintype "power_in"))
      (node (ref "DD105") (pin "5") (pinfunction "VCC_5") (pintype "power_in"))
      (node (ref "L100") (pin "1") (pinfunction "1_1") (pintype "passive"))
      (node (ref "R101") (pin "1") (pinfunction "1_1") (pintype "passive"))
      (node (ref "R103") (pin "1") (pinfunction "1_1") (pintype "passive"))
      (node (ref "R104") (pin "1") (pinfunction "1_1") (pintype "passive"))
      (node (ref "R119") (pin "1") (pinfunction "1_1") (pintype "passive"))
      (node (ref "R122") (pin "1") (pinfunction "1_1") (pintype "passive"))
      (node (ref "R123") (pin "1") (pinfunction "1_1") (pintype "passive"))
      (node (ref "R124") (pin "1") (pinfunction "1_1") (pintype "passive"))
      (node (ref "VT100") (pin "C") (pinfunction "C_C") (pintype "passive"))
      (node (ref "VT101") (pin "C") (pinfunction "C_C") (pintype "passive"))
      (node (ref "VT102") (pin "C") (pinfunction "C_C") (pintype "passive"))
      (node (ref "VT104") (pin "C") (pinfunction "C_C") (pintype "passive"))
      (node (ref "XP100") (pin "1") (pinfunction "1_1") (pintype "passive"))
    )
    (net (code "59") (name "VCCA") (class "Default")
      (node (ref "C107") (pin "1") (pinfunction "1_1") (pintype "passive"))
      (node (ref "C108") (pin "1") (pinfunction "1_1") (pintype "passive"))
      (node (ref "D100") (pin "9") (pinfunction "VDDA_9") (pintype "passive"))
      (node (ref "L100") (pin "2") (pinfunction "2_2") (pintype "passive"))
      (node (ref "VT103") (pin "C") (pinfunction "C_C") (pintype "passive"))
    )
    (net (code "60") (name "unconnected-(D100-PD0(HS){slash}TIM3_CH2[TIM1_BKIN][CLK_CCO]-Pad25)") (class "Default")
      (node (ref "D100") (pin "25") (pinfunction "PD0(HS)/TIM3_CH2[TIM1_BKIN][CLK_CCO]_25") (pintype "passive"))
    )
    (net (code "61") (name "unconnected-(D100-PD3(HS){slash}TIM2_CH2[ADC_ETR]-Pad28)") (class "Default")
      (node (ref "D100") (pin "28") (pinfunction "PD3(HS)/TIM2_CH2[ADC_ETR]_28") (pintype "passive"))
    )
    (net (code "62") (name "unconnected-(D100-PD4(HS){slash}TIM2_CH1[BEEP]-Pad29)") (class "Default")
      (node (ref "D100") (pin "29") (pinfunction "PD4(HS)/TIM2_CH1[BEEP]_29") (pintype "passive"))
    )
    (net (code "63") (name "unconnected-(D100-PD5{slash}UART2_TX-Pad30)") (class "Default")
      (node (ref "D100") (pin "30") (pinfunction "PD5/UART2_TX_30") (pintype "passive"))
    )
    (net (code "64") (name "unconnected-(D100-PD6{slash}UART2_RX-Pad31)") (class "Default")
      (node (ref "D100") (pin "31") (pinfunction "PD6/UART2_RX_31") (pintype "passive"))
    )
    (net (code "65") (name "unconnected-(D102-OS-Pad3)") (class "Default")
      (node (ref "D102") (pin "3") (pinfunction "OS_3") (pintype "passive+no_connect"))
    )
  )
)
